# 8161_-FSK_V1_28.net
KiCad netlist of a schematic drawn in Altium Designer
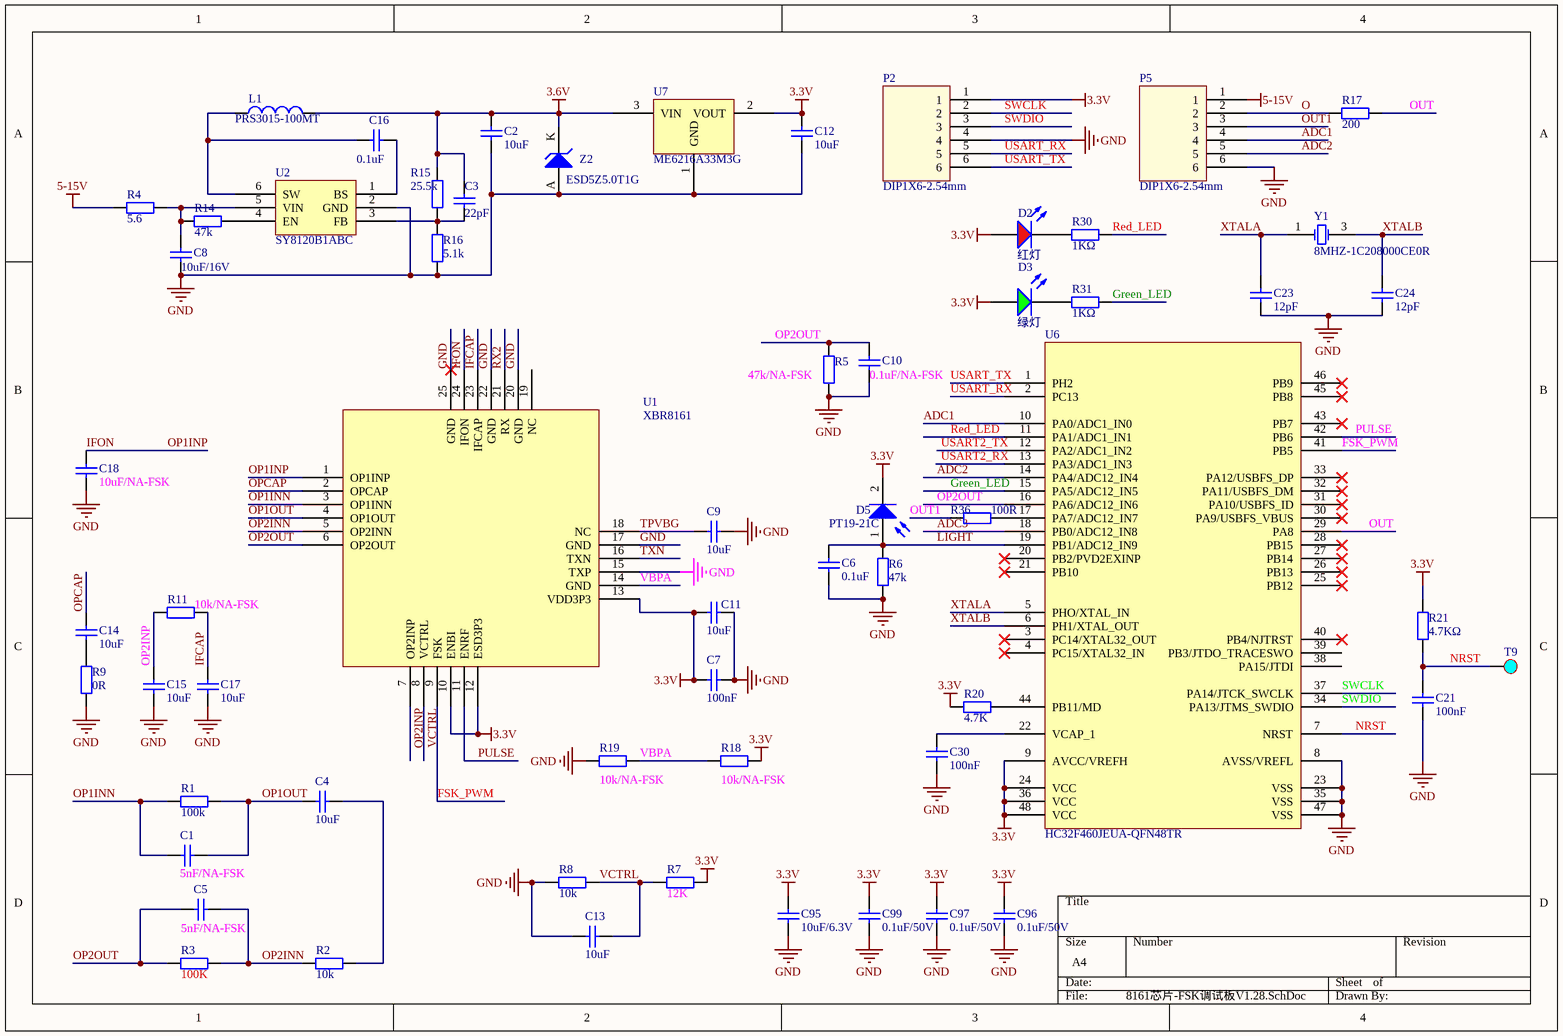
[diagram p0: 8161芯片-FSK调试板V1.28.SchDoc]

(export (version "E")
  (design (tool "Eeschema 10.0.6"))
  (components
    (comp (ref "C1")
      (value "5nF/NA-FSK")
      (footprint "C0402")
      (description "Capacitor")
      (fields (field (name "PUBLISHER") "Altium Limited"))
      (libsource (lib "Miscellaneous Devices") (part "Cap"))
    )
    (comp (ref "C2")
      (value "10uF")
      (footprint "C0402")
      (description "Capacitor")
      (fields (field (name "PUBLISHER") "Altium Limited"))
      (libsource (lib "Miscellaneous Devices") (part "Cap"))
    )
    (comp (ref "C3")
      (value "22pF")
      (footprint "C0402")
      (description "Capacitor")
      (fields (field (name "PUBLISHER") "Altium Limited"))
      (libsource (lib "Miscellaneous Devices") (part "Cap"))
    )
    (comp (ref "C4")
      (value "10uF")
      (footprint "C0402")
      (description "Capacitor")
      (fields (field (name "PUBLISHER") "Altium Limited"))
      (libsource (lib "Miscellaneous Devices") (part "Cap"))
    )
    (comp (ref "C5")
      (value "5nF/NA-FSK")
      (footprint "C0402")
      (description "Capacitor")
      (fields (field (name "PUBLISHER") "Altium Limited"))
      (libsource (lib "Miscellaneous Devices") (part "Cap"))
    )
    (comp (ref "C6")
      (value "0.1uF")
      (footprint "C0402")
      (description "Capacitor")
      (fields (field (name "PUBLISHER") "Altium Limited"))
      (libsource (lib "Miscellaneous Devices") (part "Cap"))
    )
    (comp (ref "C7")
      (value "100nF")
      (footprint "C0402")
      (description "Capacitor")
      (fields (field (name "PUBLISHER") "Altium Limited"))
      (libsource (lib "Miscellaneous Devices") (part "Cap"))
    )
    (comp (ref "C8")
      (value "10uF/16V")
      (footprint "C0603")
      (description "Capacitor")
      (fields (field (name "PUBLISHER") "Altium Limited"))
      (libsource (lib "Miscellaneous Devices") (part "Cap"))
    )
    (comp (ref "C9")
      (value "10uF")
      (footprint "C0402")
      (description "Capacitor")
      (fields (field (name "PUBLISHER") "Altium Limited"))
      (libsource (lib "Miscellaneous Devices") (part "Cap"))
    )
    (comp (ref "C10")
      (value "0.1uF/NA-FSK")
      (footprint "C0402")
      (description "Capacitor")
      (fields (field (name "PUBLISHER") "Altium Limited"))
      (libsource (lib "Miscellaneous Devices") (part "Cap"))
    )
    (comp (ref "C11")
      (value "10uF")
      (footprint "C0402")
      (description "Capacitor")
      (fields (field (name "PUBLISHER") "Altium Limited"))
      (libsource (lib "Miscellaneous Devices") (part "Cap"))
    )
    (comp (ref "C12")
      (value "10uF")
      (footprint "C0402")
      (description "Capacitor")
      (fields (field (name "PUBLISHER") "Altium Limited"))
      (libsource (lib "Miscellaneous Devices") (part "Cap"))
    )
    (comp (ref "C13")
      (value "10uF")
      (footprint "C0402")
      (description "Capacitor")
      (fields (field (name "PUBLISHER") "Altium Limited"))
      (libsource (lib "Miscellaneous Devices") (part "Cap"))
    )
    (comp (ref "C14")
      (value "10uF")
      (footprint "C0402")
      (description "Capacitor")
      (fields (field (name "PUBLISHER") "Altium Limited"))
      (libsource (lib "Miscellaneous Devices") (part "Cap"))
    )
    (comp (ref "C15")
      (value "10uF")
      (footprint "C0402")
      (description "Capacitor")
      (fields (field (name "PUBLISHER") "Altium Limited"))
      (libsource (lib "Miscellaneous Devices") (part "Cap"))
    )
    (comp (ref "C16")
      (value "0.1uF")
      (footprint "C0402")
      (description "Capacitor")
      (fields (field (name "PUBLISHER") "Altium Limited"))
      (libsource (lib "Miscellaneous Devices") (part "Cap"))
    )
    (comp (ref "C17")
      (value "10uF")
      (footprint "C0402")
      (description "Capacitor")
      (fields (field (name "PUBLISHER") "Altium Limited"))
      (libsource (lib "Miscellaneous Devices") (part "Cap"))
    )
    (comp (ref "C18")
      (value "10uF/NA-FSK")
      (footprint "C0402")
      (description "Capacitor")
      (fields (field (name "PUBLISHER") "Altium Limited"))
      (libsource (lib "Miscellaneous Devices") (part "Cap"))
    )
    (comp (ref "C21")
      (value "100nF")
      (footprint "C0402")
      (description "贴片电容")
      (libsource (lib "Miscellaneous Devices LC") (part "0402 100nF (104) 10% 16V"))
    )
    (comp (ref "C23")
      (value "12pF")
      (footprint "C0402")
      (description "贴片电容")
      (libsource (lib "Cap") (part "0402 22pF (220) 5% 50V"))
    )
    (comp (ref "C24")
      (value "12pF")
      (footprint "C0402")
      (description "贴片电容")
      (libsource (lib "Cap") (part "0402 22pF (220) 5% 50V"))
    )
    (comp (ref "C30")
      (value "100nF")
      (footprint "C0402")
      (description "Capacitor")
      (fields (field (name "PUBLISHER") "Altium Limited"))
      (libsource (lib "Miscellaneous Devices") (part "Cap"))
    )
    (comp (ref "C95")
      (value "10uF/6.3V")
      (footprint "C0402")
      (description "贴片电容")
      (libsource (lib "Cap") (part "0402 2.2nF (222) 10% 50V"))
    )
    (comp (ref "C96")
      (value "0.1uF/50V")
      (footprint "C0402")
      (description "贴片电容")
      (libsource (lib "Cap") (part "0402 2.2nF (222) 10% 50V"))
    )
    (comp (ref "C97")
      (value "0.1uF/50V")
      (footprint "C0402")
      (description "贴片电容")
      (libsource (lib "Cap") (part "0402 2.2nF (222) 10% 50V"))
    )
    (comp (ref "C99")
      (value "0.1uF/50V")
      (footprint "C0402")
      (description "贴片电容")
      (libsource (lib "Cap") (part "0402 2.2nF (222) 10% 50V"))
    )
    (comp (ref "D2")
      (value "红灯")
      (footprint "LC-0603_LED_S1")
      (description "发光二极管")
      (libsource (lib "Miscellaneous Devices LC") (part "0603 红灯"))
    )
    (comp (ref "D3")
      (value "绿灯")
      (footprint "LC-0603_LED_S1")
      (description "发光二极管")
      (libsource (lib "30x35雷达微动底板V0.2") (part "0603 红灯"))
    )
    (comp (ref "D5")
      (value "PT19-21C")
      (footprint "LED-0603")
      (description "Photosensitive Diode")
      (fields (field (name "PUBLISHER") "Altium Limited"))
      (libsource (lib "Miscellaneous Devices") (part "Photo Sen"))
    )
    (comp (ref "L1")
      (value "PRS3015-100MT")
      (footprint "PRS3015")
      (description "Inductor")
      (fields (field (name "PUBLISHER") "Altium Limited"))
      (libsource (lib "Miscellaneous Devices") (part "Inductor"))
    )
    (comp (ref "P2")
      (value "DIP1X6-2.54mm")
      (footprint "DIP1X6-2.54")
      (libsource (lib "30x35雷达微动底板V0.2") (part "DIP1X6-2.54mm"))
    )
    (comp (ref "P5")
      (value "DIP1X6-2.54mm")
      (footprint "DIP1X6-2.54")
      (libsource (lib "30x35雷达微动底板V0.2") (part "DIP1X6-2.54mm"))
    )
    (comp (ref "R1")
      (value "100k")
      (footprint "R0402")
      (description "Resistor")
      (fields (field (name "PUBLISHER") "Altium Limited"))
      (libsource (lib "") (part "Res2_3"))
    )
    (comp (ref "R2")
      (value "10k")
      (footprint "R0402")
      (description "Resistor")
      (fields (field (name "PUBLISHER") "Altium Limited"))
      (libsource (lib "Miscellaneous Devices") (part "Res2"))
    )
    (comp (ref "R3")
      (value "100K")
      (footprint "R0402")
      (description "Resistor")
      (fields (field (name "PUBLISHER") "Altium Limited"))
      (libsource (lib "Miscellaneous Devices") (part "Res2"))
    )
    (comp (ref "R4")
      (value "5.6")
      (footprint "R0402")
      (description "Resistor")
      (fields (field (name "PUBLISHER") "Altium Limited"))
      (libsource (lib "") (part "Res2_4"))
    )
    (comp (ref "R5")
      (value "47k/NA-FSK")
      (footprint "R0402")
      (description "Resistor")
      (fields (field (name "PUBLISHER") "Altium Limited"))
      (libsource (lib "") (part "Res2_1"))
    )
    (comp (ref "R6")
      (value "47k")
      (footprint "R0402")
      (description "Resistor")
      (fields (field (name "PUBLISHER") "Altium Limited"))
      (libsource (lib "") (part "Res2_1"))
    )
    (comp (ref "R7")
      (value "12K")
      (footprint "R0402")
      (description "Resistor")
      (fields (field (name "PUBLISHER") "Altium Limited"))
      (libsource (lib "Miscellaneous Devices") (part "Res2"))
    )
    (comp (ref "R8")
      (value "10k")
      (footprint "R0402")
      (description "Resistor")
      (fields (field (name "PUBLISHER") "Altium Limited"))
      (libsource (lib "Miscellaneous Devices") (part "Res2"))
    )
    (comp (ref "R9")
      (value "0R")
      (footprint "R0402")
      (description "Resistor")
      (fields (field (name "PUBLISHER") "Altium Limited"))
      (libsource (lib "") (part "Res2_1"))
    )
    (comp (ref "R11")
      (value "10k/NA-FSK")
      (footprint "R0402")
      (description "Resistor")
      (fields (field (name "PUBLISHER") "Altium Limited"))
      (libsource (lib "Miscellaneous Devices") (part "Res2"))
    )
    (comp (ref "R14")
      (value "47k")
      (footprint "R0402")
      (description "Resistor")
      (fields (field (name "PUBLISHER") "Altium Limited"))
      (libsource (lib "Miscellaneous Devices") (part "Res2"))
    )
    (comp (ref "R15")
      (value "25.5k")
      (footprint "R0402")
      (description "Resistor")
      (fields (field (name "PUBLISHER") "Altium Limited"))
      (libsource (lib "") (part "Res2_2"))
    )
    (comp (ref "R16")
      (value "5.1k")
      (footprint "R0402")
      (description "Resistor")
      (fields (field (name "PUBLISHER") "Altium Limited"))
      (libsource (lib "") (part "Res2_2"))
    )
    (comp (ref "R17")
      (value "200")
      (footprint "R0402")
      (description "Resistor")
      (fields (field (name "PUBLISHER") "Altium Limited"))
      (libsource (lib "") (part "Res2_3"))
    )
    (comp (ref "R18")
      (value "10k/NA-FSK")
      (footprint "R0402")
      (description "Resistor")
      (fields (field (name "PUBLISHER") "Altium Limited"))
      (libsource (lib "Miscellaneous Devices") (part "Res2"))
    )
    (comp (ref "R19")
      (value "10k/NA-FSK")
      (footprint "R0402")
      (description "Resistor")
      (fields (field (name "PUBLISHER") "Altium Limited"))
      (libsource (lib "Miscellaneous Devices") (part "Res2"))
    )
    (comp (ref "R20")
      (value "4.7K")
      (footprint "R0402")
      (description "Resistor")
      (fields (field (name "PUBLISHER") "Altium Limited"))
      (libsource (lib "") (part "Res2_3"))
    )
    (comp (ref "R21")
      (value "4.7KΩ")
      (footprint "R0402")
      (description "贴片电阻")
      (libsource (lib "") (part "0402 4.7KΩ (4701) 1%_1"))
    )
    (comp (ref "R30")
      (value "1KΩ")
      (footprint "R0402")
      (description "贴片电阻")
      (libsource (lib "Miscellaneous Devices LC") (part "0402 1KΩ (1001) 1%"))
    )
    (comp (ref "R31")
      (value "1KΩ")
      (footprint "R0402")
      (description "贴片电阻")
      (libsource (lib "Miscellaneous Devices LC") (part "0402 1KΩ (1001) 1%"))
    )
    (comp (ref "R36")
      (value "100R")
      (footprint "R0402")
      (description "贴片电阻")
      (libsource (lib "Miscellaneous Devices LC") (part "0402 4.7KΩ (4701) 1%"))
    )
    (comp (ref "T9")
      (value "~")
      (footprint "TestPoints")
      (description "TestPoints")
      (libsource (lib "标准原理图库（特种板）") (part "TestPoints"))
    )
    (comp (ref "U1")
      (value "XBR8161")
      (footprint "QFN24")
      (libsource (lib "altium-import") (part "root_0_XBR8161_"))
    )
    (comp (ref "U2") (value "SY8120B1ABC") (footprint "SOT-23-6") (libsource (lib "Schlib1") (part "H9108")))
    (comp (ref "U6")
      (value "HC32F460JEUA-QFN48TR")
      (footprint "QFN48-5X5mm")
      (libsource (lib "LD-ShouShi-Module-V1.0") (part "HC32F460JETA-LQFP48"))
    )
    (comp (ref "U7")
      (value "ME6216A33M3G")
      (footprint "SOT-23-L")
      (libsource (lib "Schlib1") (part "SSP6206"))
    )
    (comp (ref "Y1")
      (value "8MHZ-1C208000CE0R")
      (footprint "OSC-SMD_3225")
      (description "贴片晶振")
      (libsource (lib "CrystalOscillator") (part "SMD-3225_4P  25MHZ 12PF 10PPM"))
    )
    (comp (ref "Z2")
      (value "ESD5Z5.0T1G")
      (footprint "SOD323")
      (description "Zener Diode")
      (fields (field (name "PUBLISHER") "Altium Limited"))
      (libsource (lib "Miscellaneous Devices") (part "D Zener"))
    )
  )
  (nets
    (net (code "1") (name "/ADC1") (class "Default")
      (node (ref "P5") (pin "4") (pinfunction "4_4") (pintype "passive"))
      (node (ref "U6") (pin "10") (pinfunction "PA0/ADC1_IN0_10") (pintype "passive"))
    )
    (net (code "2") (name "/ADC2") (class "Default")
      (node (ref "P5") (pin "5") (pinfunction "5_5") (pintype "passive"))
      (node (ref "U6") (pin "14") (pinfunction "PA4/ADC12_IN4_14") (pintype "passive"))
    )
    (net (code "3") (name "/ADC3") (class "Default")
      (node (ref "U6") (pin "18") (pinfunction "PB0/ADC12_IN8_18") (pintype "passive"))
    )
    (net (code "4") (name "/FSK_PWM") (class "Default")
      (node (ref "U1") (pin "9") (pinfunction "FSK_9") (pintype "passive"))
      (node (ref "U6") (pin "41") (pinfunction "PB5_41") (pintype "passive"))
    )
    (net (code "5") (name "/Green_LED") (class "Default")
      (node (ref "R31") (pin "1") (pinfunction "1_1") (pintype "passive"))
      (node (ref "U6") (pin "15") (pinfunction "PA5/ADC12_IN5_15") (pintype "passive"))
    )
    (net (code "6") (name "/IFCAP") (class "Default")
      (node (ref "C17") (pin "2") (pinfunction "2_2") (pintype "passive"))
      (node (ref "R11") (pin "1") (pinfunction "1_1") (pintype "passive"))
      (node (ref "U1") (pin "23") (pinfunction "IFCAP_23") (pintype "passive"))
    )
    (net (code "7") (name "/IFON") (class "Default")
      (node (ref "C18") (pin "2") (pinfunction "2_2") (pintype "passive"))
      (node (ref "U1") (pin "1") (pinfunction "OP1INP_1") (pintype "passive"))
      (node (ref "U1") (pin "24") (pinfunction "IFON_24") (pintype "passive"))
    )
    (net (code "8") (name "/LIGHT") (class "Default")
      (node (ref "C6") (pin "1") (pinfunction "1_1") (pintype "passive"))
      (node (ref "D5") (pin "1") (pinfunction "A_1") (pintype "passive"))
      (node (ref "R6") (pin "1") (pinfunction "1_1") (pintype "passive"))
      (node (ref "U6") (pin "19") (pinfunction "PB1/ADC12_IN9_19") (pintype "passive"))
    )
    (net (code "9") (name "/NRST") (class "Default")
      (node (ref "C21") (pin "2") (pinfunction "2_2") (pintype "passive"))
      (node (ref "R21") (pin "1") (pinfunction "1_1") (pintype "passive"))
      (node (ref "T9") (pin "1") (pinfunction "1_1") (pintype "passive"))
      (node (ref "U6") (pin "7") (pinfunction "NRST_7") (pintype "passive"))
    )
    (net (code "10") (name "/O") (class "Default")
      (node (ref "P5") (pin "2") (pinfunction "2_2") (pintype "passive"))
      (node (ref "R17") (pin "1") (pinfunction "1_1") (pintype "passive"))
    )
    (net (code "11") (name "/OP1INN") (class "Default")
      (node (ref "C1") (pin "2") (pinfunction "2_2") (pintype "passive"))
      (node (ref "R1") (pin "1") (pinfunction "1_1") (pintype "passive"))
      (node (ref "U1") (pin "3") (pinfunction "OP1INN_3") (pintype "passive"))
    )
    (net (code "12") (name "/OP1OUT") (class "Default")
      (node (ref "C1") (pin "1") (pinfunction "1_1") (pintype "passive"))
      (node (ref "C4") (pin "2") (pinfunction "2_2") (pintype "passive"))
      (node (ref "R1") (pin "2") (pinfunction "2_2") (pintype "passive"))
      (node (ref "U1") (pin "4") (pinfunction "OP1OUT_4") (pintype "passive"))
    )
    (net (code "13") (name "/OP2INN") (class "Default")
      (node (ref "C5") (pin "2") (pinfunction "2_2") (pintype "passive"))
      (node (ref "R2") (pin "2") (pinfunction "2_2") (pintype "passive"))
      (node (ref "R3") (pin "1") (pinfunction "1_1") (pintype "passive"))
      (node (ref "U1") (pin "5") (pinfunction "OP2INN_5") (pintype "passive"))
    )
    (net (code "14") (name "/OP2INP") (class "Default")
      (node (ref "C15") (pin "1") (pinfunction "1_1") (pintype "passive"))
      (node (ref "R11") (pin "2") (pinfunction "2_2") (pintype "passive"))
      (node (ref "U1") (pin "7") (pinfunction "OP2INP_7") (pintype "passive"))
    )
    (net (code "15") (name "/OP2OUT") (class "Default")
      (node (ref "C10") (pin "1") (pinfunction "1_1") (pintype "passive"))
      (node (ref "C5") (pin "1") (pinfunction "1_1") (pintype "passive"))
      (node (ref "R3") (pin "2") (pinfunction "2_2") (pintype "passive"))
      (node (ref "R5") (pin "1") (pinfunction "1_1") (pintype "passive"))
      (node (ref "U1") (pin "6") (pinfunction "OP2OUT_6") (pintype "passive"))
      (node (ref "U6") (pin "16") (pinfunction "PA6/ADC12_IN6_16") (pintype "passive"))
    )
    (net (code "16") (name "/OPCAP") (class "Default")
      (node (ref "C14") (pin "2") (pinfunction "2_2") (pintype "passive"))
      (node (ref "U1") (pin "2") (pinfunction "OPCAP_2") (pintype "passive"))
    )
    (net (code "17") (name "/OUT") (class "Default")
      (node (ref "R17") (pin "2") (pinfunction "2_2") (pintype "passive"))
      (node (ref "U6") (pin "29") (pinfunction "PA8_29") (pintype "passive"))
    )
    (net (code "18") (name "/OUT1") (class "Default")
      (node (ref "P5") (pin "3") (pinfunction "3_3") (pintype "passive"))
      (node (ref "R36") (pin "2") (pinfunction "2_2") (pintype "passive"))
    )
    (net (code "19") (name "/PULSE") (class "Default")
      (node (ref "U1") (pin "11") (pinfunction "ENRF_11") (pintype "passive"))
      (node (ref "U6") (pin "42") (pinfunction "PB6_42") (pintype "passive"))
    )
    (net (code "20") (name "/RX2") (class "Default")
      (node (ref "U1") (pin "21") (pinfunction "RX_21") (pintype "passive"))
    )
    (net (code "21") (name "/Red_LED") (class "Default")
      (node (ref "R30") (pin "1") (pinfunction "1_1") (pintype "passive"))
      (node (ref "U6") (pin "11") (pinfunction "PA1/ADC1_IN1_11") (pintype "passive"))
    )
    (net (code "22") (name "/SWCLK") (class "Default")
      (node (ref "P2") (pin "2") (pinfunction "2_2") (pintype "passive"))
      (node (ref "U6") (pin "37") (pinfunction "PA14/JTCK_SWCLK_37") (pintype "passive"))
    )
    (net (code "23") (name "/SWDIO") (class "Default")
      (node (ref "P2") (pin "3") (pinfunction "3_3") (pintype "passive"))
      (node (ref "U6") (pin "34") (pinfunction "PA13/JTMS_SWDIO_34") (pintype "passive"))
    )
    (net (code "24") (name "/TPVBG") (class "Default")
      (node (ref "C9") (pin "2") (pinfunction "2_2") (pintype "passive"))
      (node (ref "U1") (pin "18") (pinfunction "NC_18") (pintype "passive"))
    )
    (net (code "25") (name "/TXN") (class "Default")
      (node (ref "U1") (pin "16") (pinfunction "TXN_16") (pintype "passive"))
    )
    (net (code "26") (name "/USART2_RX") (class "Default")
      (node (ref "U6") (pin "13") (pinfunction "PA3/ADC1_IN3_13") (pintype "passive"))
    )
    (net (code "27") (name "/USART2_TX") (class "Default")
      (node (ref "U6") (pin "12") (pinfunction "PA2/ADC1_IN2_12") (pintype "passive"))
    )
    (net (code "28") (name "/USART_RX") (class "Default")
      (node (ref "P2") (pin "5") (pinfunction "5_5") (pintype "passive"))
      (node (ref "U6") (pin "2") (pinfunction "PC13_2") (pintype "passive"))
    )
    (net (code "29") (name "/USART_TX") (class "Default")
      (node (ref "P2") (pin "6") (pinfunction "6_6") (pintype "passive"))
      (node (ref "U6") (pin "1") (pinfunction "PH2_1") (pintype "passive"))
    )
    (net (code "30") (name "/VBPA") (class "Default")
      (node (ref "R18") (pin "2") (pinfunction "2_2") (pintype "passive"))
      (node (ref "R19") (pin "1") (pinfunction "1_1") (pintype "passive"))
      (node (ref "U1") (pin "14") (pinfunction "GND_14") (pintype "passive"))
    )
    (net (code "31") (name "/VCTRL") (class "Default")
      (node (ref "C13") (pin "1") (pinfunction "1_1") (pintype "passive"))
      (node (ref "R7") (pin "2") (pinfunction "2_2") (pintype "passive"))
      (node (ref "R8") (pin "1") (pinfunction "1_1") (pintype "passive"))
      (node (ref "U1") (pin "8") (pinfunction "VCTRL_8") (pintype "passive"))
    )
    (net (code "32") (name "/XTALA") (class "Default")
      (node (ref "C23") (pin "2") (pinfunction "2_2") (pintype "passive"))
      (node (ref "U6") (pin "5") (pinfunction "PHO/XTAL_IN_5") (pintype "passive"))
      (node (ref "Y1") (pin "1") (pinfunction "OSC1_1") (pintype "passive"))
    )
    (net (code "33") (name "/XTALB") (class "Default")
      (node (ref "C24") (pin "2") (pinfunction "2_2") (pintype "passive"))
      (node (ref "U6") (pin "6") (pinfunction "PH1/XTAL_OUT_6") (pintype "passive"))
      (node (ref "Y1") (pin "3") (pinfunction "OSC2_3") (pintype "passive"))
    )
    (net (code "34") (name "3.3V") (class "Default")
      (node (ref "C11") (pin "2") (pinfunction "2_2") (pintype "passive"))
      (node (ref "C12") (pin "1") (pinfunction "1_1") (pintype "passive"))
      (node (ref "C7") (pin "2") (pinfunction "2_2") (pintype "passive"))
      (node (ref "C95") (pin "1") (pinfunction "1_1") (pintype "passive"))
      (node (ref "C96") (pin "1") (pinfunction "1_1") (pintype "passive"))
      (node (ref "C97") (pin "1") (pinfunction "1_1") (pintype "passive"))
      (node (ref "C99") (pin "1") (pinfunction "1_1") (pintype "passive"))
      (node (ref "D2") (pin "A") (pinfunction "A_A") (pintype "passive"))
      (node (ref "D3") (pin "A") (pinfunction "A_A") (pintype "passive"))
      (node (ref "D5") (pin "2") (pinfunction "K_2") (pintype "passive"))
      (node (ref "P2") (pin "1") (pinfunction "1_1") (pintype "passive"))
      (node (ref "R18") (pin "1") (pinfunction "1_1") (pintype "passive"))
      (node (ref "R20") (pin "1") (pinfunction "1_1") (pintype "passive"))
      (node (ref "R21") (pin "2") (pinfunction "2_2") (pintype "passive"))
      (node (ref "R7") (pin "1") (pinfunction "1_1") (pintype "passive"))
      (node (ref "U1") (pin "10") (pinfunction "ENBI_10") (pintype "passive"))
      (node (ref "U1") (pin "12") (pinfunction "ESD3P3_12") (pintype "passive"))
      (node (ref "U1") (pin "13") (pinfunction "VDD3P3_13") (pintype "passive"))
      (node (ref "U6") (pin "24") (pinfunction "VCC_24") (pintype "passive"))
      (node (ref "U6") (pin "36") (pinfunction "VCC_36") (pintype "passive"))
      (node (ref "U6") (pin "48") (pinfunction "VCC_48") (pintype "passive"))
      (node (ref "U6") (pin "9") (pinfunction "AVCC/VREFH_9") (pintype "passive"))
      (node (ref "U7") (pin "2") (pinfunction "VOUT_2") (pintype "passive"))
    )
    (net (code "35") (name "3.6V") (class "Default")
      (node (ref "C2") (pin "1") (pinfunction "1_1") (pintype "passive"))
      (node (ref "C3") (pin "2") (pinfunction "2_2") (pintype "passive"))
      (node (ref "L1") (pin "2") (pinfunction "2_2") (pintype "passive"))
      (node (ref "R15") (pin "2") (pinfunction "2_2") (pintype "passive"))
      (node (ref "U7") (pin "3") (pinfunction "VIN_3") (pintype "passive"))
      (node (ref "Z2") (pin "K") (pinfunction "K_K") (pintype "passive"))
    )
    (net (code "36") (name "5-15V") (class "Default")
      (node (ref "P5") (pin "1") (pinfunction "1_1") (pintype "passive"))
      (node (ref "R4") (pin "1") (pinfunction "1_1") (pintype "passive"))
    )
    (net (code "37") (name "GND") (class "Default")
      (node (ref "C10") (pin "2") (pinfunction "2_2") (pintype "passive"))
      (node (ref "C11") (pin "1") (pinfunction "1_1") (pintype "passive"))
      (node (ref "C12") (pin "2") (pinfunction "2_2") (pintype "passive"))
      (node (ref "C13") (pin "2") (pinfunction "2_2") (pintype "passive"))
      (node (ref "C15") (pin "2") (pinfunction "2_2") (pintype "passive"))
      (node (ref "C17") (pin "1") (pinfunction "1_1") (pintype "passive"))
      (node (ref "C18") (pin "1") (pinfunction "1_1") (pintype "passive"))
      (node (ref "C2") (pin "2") (pinfunction "2_2") (pintype "passive"))
      (node (ref "C21") (pin "1") (pinfunction "1_1") (pintype "passive"))
      (node (ref "C23") (pin "1") (pinfunction "1_1") (pintype "passive"))
      (node (ref "C24") (pin "1") (pinfunction "1_1") (pintype "passive"))
      (node (ref "C30") (pin "2") (pinfunction "2_2") (pintype "passive"))
      (node (ref "C6") (pin "2") (pinfunction "2_2") (pintype "passive"))
      (node (ref "C7") (pin "1") (pinfunction "1_1") (pintype "passive"))
      (node (ref "C8") (pin "2") (pinfunction "2_2") (pintype "passive"))
      (node (ref "C9") (pin "1") (pinfunction "1_1") (pintype "passive"))
      (node (ref "C95") (pin "2") (pinfunction "2_2") (pintype "passive"))
      (node (ref "C96") (pin "2") (pinfunction "2_2") (pintype "passive"))
      (node (ref "C97") (pin "2") (pinfunction "2_2") (pintype "passive"))
      (node (ref "C99") (pin "2") (pinfunction "2_2") (pintype "passive"))
      (node (ref "P2") (pin "4") (pinfunction "4_4") (pintype "passive"))
      (node (ref "P5") (pin "6") (pinfunction "6_6") (pintype "passive"))
      (node (ref "R16") (pin "1") (pinfunction "1_1") (pintype "passive"))
      (node (ref "R19") (pin "2") (pinfunction "2_2") (pintype "passive"))
      (node (ref "R5") (pin "2") (pinfunction "2_2") (pintype "passive"))
      (node (ref "R6") (pin "2") (pinfunction "2_2") (pintype "passive"))
      (node (ref "R8") (pin "2") (pinfunction "2_2") (pintype "passive"))
      (node (ref "R9") (pin "2") (pinfunction "2_2") (pintype "passive"))
      (node (ref "U1") (pin "15") (pinfunction "TXP_15") (pintype "passive"))
      (node (ref "U1") (pin "17") (pinfunction "GND_17") (pintype "passive"))
      (node (ref "U1") (pin "20") (pinfunction "GND_20") (pintype "passive"))
      (node (ref "U1") (pin "22") (pinfunction "GND_22") (pintype "passive"))
      (node (ref "U1") (pin "25") (pinfunction "GND_25") (pintype "passive"))
      (node (ref "U2") (pin "2") (pinfunction "GND_2") (pintype "passive"))
      (node (ref "U6") (pin "23") (pinfunction "VSS_23") (pintype "passive"))
      (node (ref "U6") (pin "35") (pinfunction "VSS_35") (pintype "passive"))
      (node (ref "U6") (pin "47") (pinfunction "VSS_47") (pintype "passive"))
      (node (ref "U6") (pin "8") (pinfunction "AVSS/VREFL_8") (pintype "passive"))
      (node (ref "U7") (pin "1") (pinfunction "GND_1") (pintype "passive"))
      (node (ref "Z2") (pin "A") (pinfunction "A_A") (pintype "passive"))
    )
    (net (code "38") (name "Net-(C4-Pad1)") (class "Default")
      (node (ref "C4") (pin "1") (pinfunction "1_1") (pintype "passive"))
      (node (ref "R2") (pin "1") (pinfunction "1_1") (pintype "passive"))
    )
    (net (code "39") (name "Net-(C14-Pad1)") (class "Default")
      (node (ref "C14") (pin "1") (pinfunction "1_1") (pintype "passive"))
      (node (ref "R9") (pin "1") (pinfunction "1_1") (pintype "passive"))
    )
    (net (code "40") (name "Net-(D2-PadK)") (class "Default")
      (node (ref "D2") (pin "K") (pinfunction "K_K") (pintype "passive"))
      (node (ref "R30") (pin "2") (pinfunction "2_2") (pintype "passive"))
    )
    (net (code "41") (name "Net-(D3-PadK)") (class "Default")
      (node (ref "D3") (pin "K") (pinfunction "K_K") (pintype "passive"))
      (node (ref "R31") (pin "2") (pinfunction "2_2") (pintype "passive"))
    )
    (net (code "42") (name "Net-(U2-BS)") (class "Default")
      (node (ref "C16") (pin "2") (pinfunction "2_2") (pintype "passive"))
      (node (ref "U2") (pin "1") (pinfunction "BS_1") (pintype "passive"))
    )
    (net (code "43") (name "Net-(U2-EN)") (class "Default")
      (node (ref "R14") (pin "1") (pinfunction "1_1") (pintype "passive"))
      (node (ref "U2") (pin "4") (pinfunction "EN_4") (pintype "passive"))
    )
    (net (code "44") (name "Net-(U2-FB)") (class "Default")
      (node (ref "C3") (pin "1") (pinfunction "1_1") (pintype "passive"))
      (node (ref "R15") (pin "1") (pinfunction "1_1") (pintype "passive"))
      (node (ref "R16") (pin "2") (pinfunction "2_2") (pintype "passive"))
      (node (ref "U2") (pin "3") (pinfunction "FB_3") (pintype "passive"))
    )
    (net (code "45") (name "Net-(U2-SW)") (class "Default")
      (node (ref "C16") (pin "1") (pinfunction "1_1") (pintype "passive"))
      (node (ref "L1") (pin "1") (pinfunction "1_1") (pintype "passive"))
      (node (ref "U2") (pin "6") (pinfunction "SW_6") (pintype "passive"))
    )
    (net (code "46") (name "Net-(U2-VIN)") (class "Default")
      (node (ref "C8") (pin "1") (pinfunction "1_1") (pintype "passive"))
      (node (ref "R14") (pin "2") (pinfunction "2_2") (pintype "passive"))
      (node (ref "R4") (pin "2") (pinfunction "2_2") (pintype "passive"))
      (node (ref "U2") (pin "5") (pinfunction "VIN_5") (pintype "passive"))
    )
    (net (code "47") (name "Net-(U6-PA7{slash}ADC12_IN7)") (class "Default")
      (node (ref "R36") (pin "1") (pinfunction "1_1") (pintype "passive"))
      (node (ref "U6") (pin "17") (pinfunction "PA7/ADC12_IN7_17") (pintype "passive"))
    )
    (net (code "48") (name "Net-(U6-PB11{slash}MD)") (class "Default")
      (node (ref "R20") (pin "2") (pinfunction "2_2") (pintype "passive"))
      (node (ref "U6") (pin "44") (pinfunction "PB11/MD_44") (pintype "passive"))
    )
    (net (code "49") (name "Net-(U6-VCAP_1)") (class "Default")
      (node (ref "C30") (pin "1") (pinfunction "1_1") (pintype "passive"))
      (node (ref "U6") (pin "22") (pinfunction "VCAP_1_22") (pintype "passive"))
    )
    (net (code "50") (name "unconnected-(U1-NC-Pad19)") (class "Default")
      (node (ref "U1") (pin "19") (pinfunction "NC_19") (pintype "passive"))
    )
    (net (code "51") (name "unconnected-(U6-PA9{slash}USBFS_VBUS-Pad30)") (class "Default")
      (node (ref "U6") (pin "30") (pinfunction "PA9/USBFS_VBUS_30") (pintype "passive+no_connect"))
    )
    (net (code "52") (name "unconnected-(U6-PA10{slash}USBFS_ID-Pad31)") (class "Default")
      (node (ref "U6") (pin "31") (pinfunction "PA10/USBFS_ID_31") (pintype "passive+no_connect"))
    )
    (net (code "53") (name "unconnected-(U6-PA11{slash}USBFS_DM-Pad32)") (class "Default")
      (node (ref "U6") (pin "32") (pinfunction "PA11/USBFS_DM_32") (pintype "passive+no_connect"))
    )
    (net (code "54") (name "unconnected-(U6-PA12{slash}USBFS_DP-Pad33)") (class "Default")
      (node (ref "U6") (pin "33") (pinfunction "PA12/USBFS_DP_33") (pintype "passive+no_connect"))
    )
    (net (code "55") (name "unconnected-(U6-PA15{slash}JTDI-Pad38)") (class "Default")
      (node (ref "U6") (pin "38") (pinfunction "PA15/JTDI_38") (pintype "passive"))
    )
    (net (code "56") (name "unconnected-(U6-PB2{slash}PVD2EXINP-Pad20)") (class "Default")
      (node (ref "U6") (pin "20") (pinfunction "PB2/PVD2EXINP_20") (pintype "passive+no_connect"))
    )
    (net (code "57") (name "unconnected-(U6-PB3{slash}JTDO_TRACESWO-Pad39)") (class "Default")
      (node (ref "U6") (pin "39") (pinfunction "PB3/JTDO_TRACESWO_39") (pintype "passive"))
    )
    (net (code "58") (name "unconnected-(U6-PB4{slash}NJTRST-Pad40)") (class "Default")
      (node (ref "U6") (pin "40") (pinfunction "PB4/NJTRST_40") (pintype "passive+no_connect"))
    )
    (net (code "59") (name "unconnected-(U6-PB7-Pad43)") (class "Default")
      (node (ref "U6") (pin "43") (pinfunction "PB7_43") (pintype "passive+no_connect"))
    )
    (net (code "60") (name "unconnected-(U6-PB8-Pad45)") (class "Default")
      (node (ref "U6") (pin "45") (pinfunction "PB8_45") (pintype "passive+no_connect"))
    )
    (net (code "61") (name "unconnected-(U6-PB9-Pad46)") (class "Default")
      (node (ref "U6") (pin "46") (pinfunction "PB9_46") (pintype "passive+no_connect"))
    )
    (net (code "62") (name "unconnected-(U6-PB10-Pad21)") (class "Default")
      (node (ref "U6") (pin "21") (pinfunction "PB10_21") (pintype "passive+no_connect"))
    )
    (net (code "63") (name "unconnected-(U6-PB12-Pad25)") (class "Default")
      (node (ref "U6") (pin "25") (pinfunction "PB12_25") (pintype "passive+no_connect"))
    )
    (net (code "64") (name "unconnected-(U6-PB13-Pad26)") (class "Default")
      (node (ref "U6") (pin "26") (pinfunction "PB13_26") (pintype "passive+no_connect"))
    )
    (net (code "65") (name "unconnected-(U6-PB14-Pad27)") (class "Default")
      (node (ref "U6") (pin "27") (pinfunction "PB14_27") (pintype "passive+no_connect"))
    )
    (net (code "66") (name "unconnected-(U6-PB15-Pad28)") (class "Default")
      (node (ref "U6") (pin "28") (pinfunction "PB15_28") (pintype "passive+no_connect"))
    )
    (net (code "67") (name "unconnected-(U6-PC14{slash}XTAL32_OUT-Pad3)") (class "Default")
      (node (ref "U6") (pin "3") (pinfunction "PC14/XTAL32_OUT_3") (pintype "passive+no_connect"))
    )
    (net (code "68") (name "unconnected-(U6-PC15{slash}XTAL32_IN-Pad4)") (class "Default")
      (node (ref "U6") (pin "4") (pinfunction "PC15/XTAL32_IN_4") (pintype "passive+no_connect"))
    )
  )
)
